# WeddingWidget.net
KiCad netlist of a schematic drawn in EAGLE
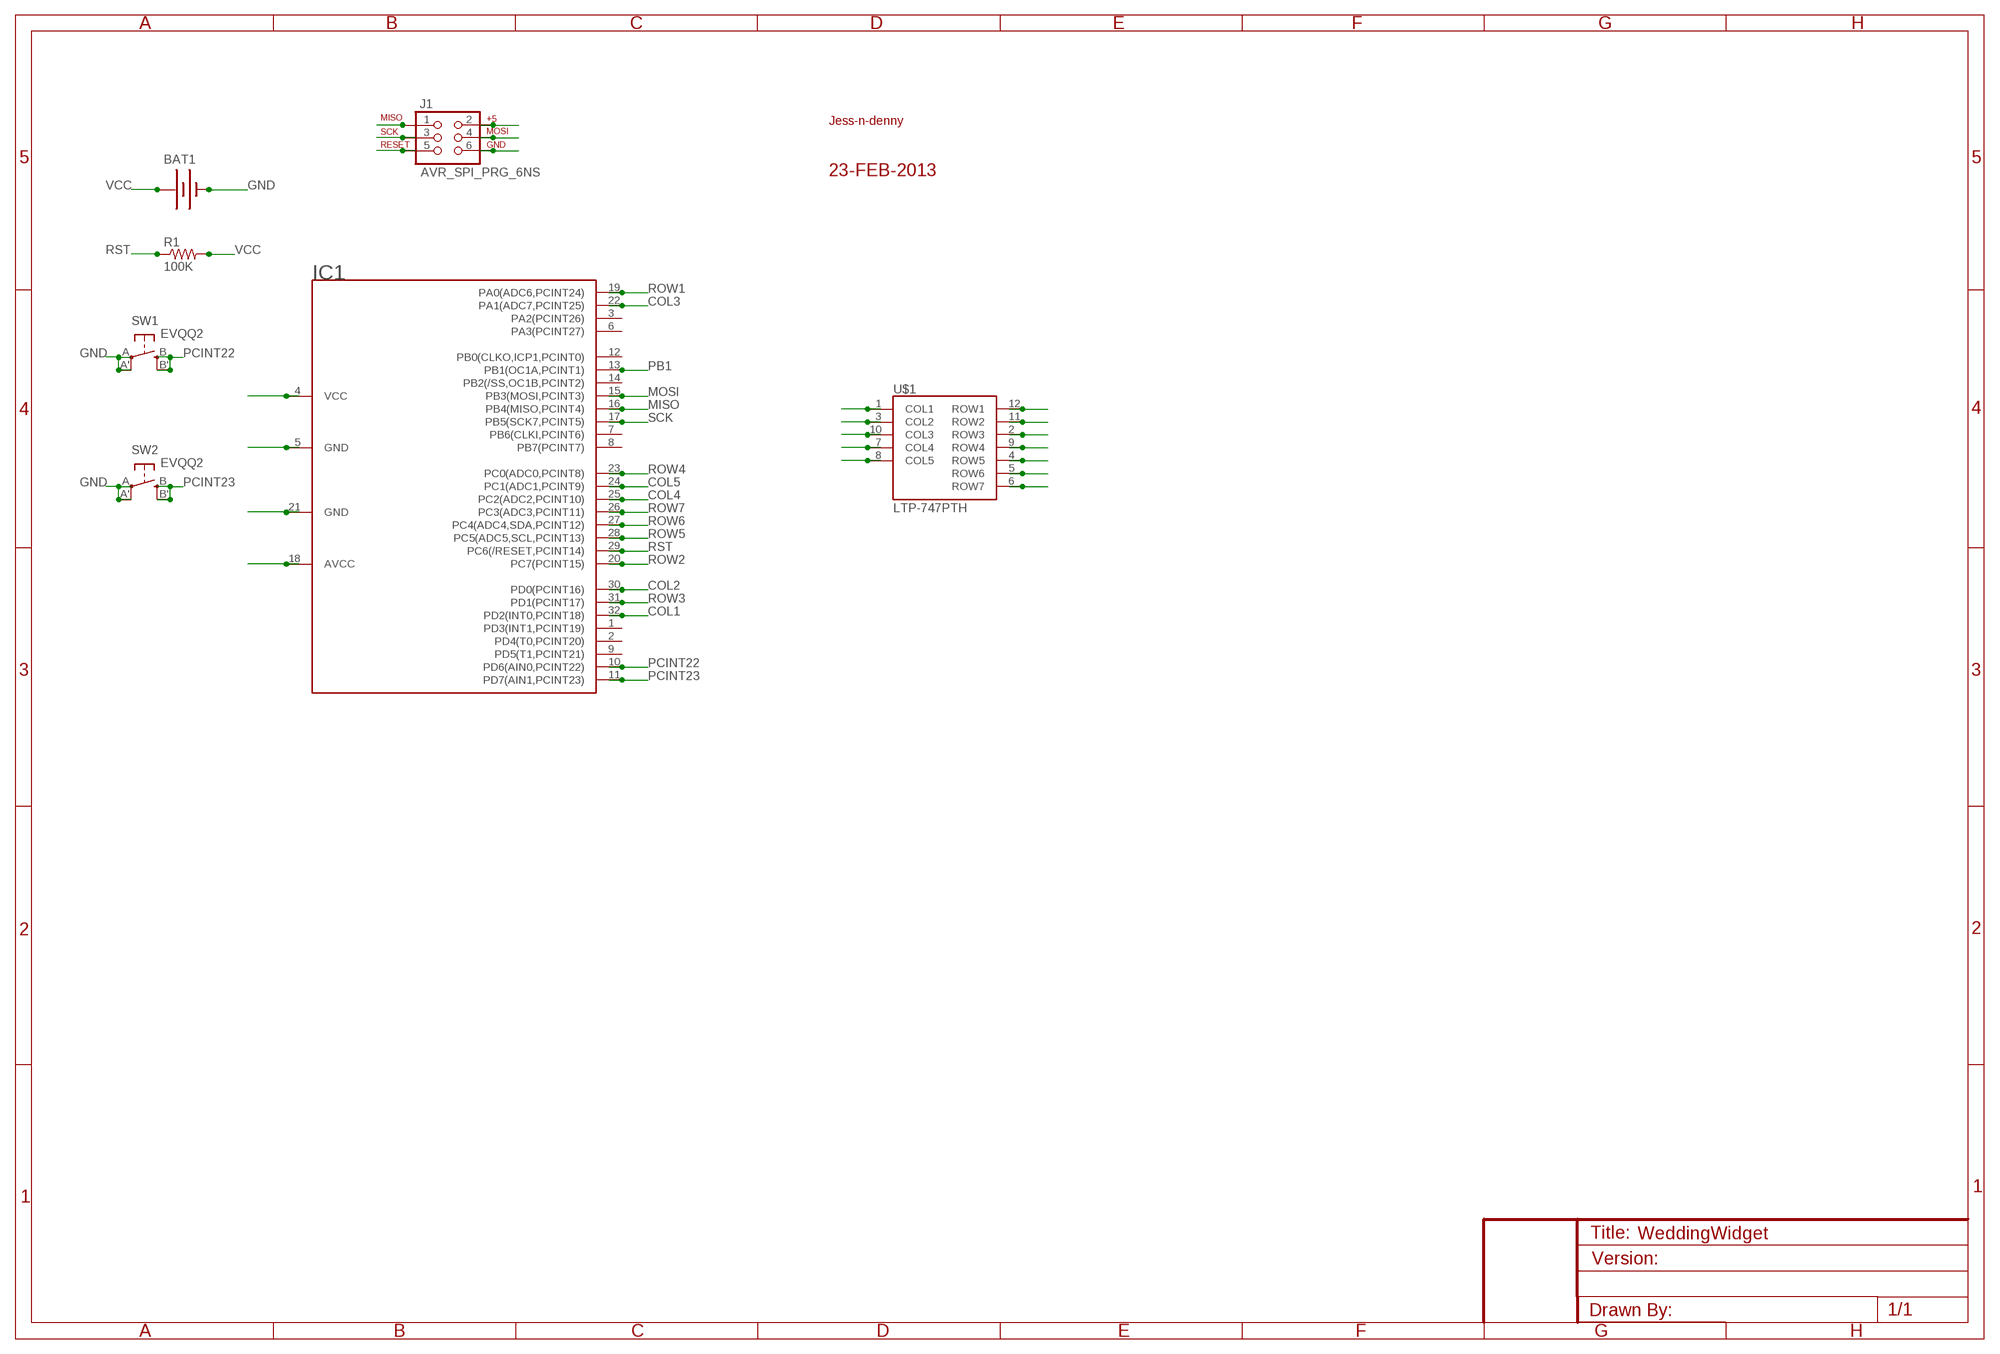
[diagram p0: schematic, sheet 1]

(export (version "E")
  (design (tool "Eeschema 10.0.6"))
  (components
    (comp (ref "BAT1")
      (value "BATTERY12MM")
      (footprint "eagle-import:BATTCON_12MM")
      (libsource (lib "eagle-import") (part "BATTERY12MM"))
    )
    (comp (ref "IC1")
      (value "ATTINY88")
      (footprint "eagle-import:TQFP32-08")
      (libsource (lib "eagle-import") (part "ATTINY88"))
    )
    (comp (ref "J1")
      (value "AVR_SPI_PRG_6NS")
      (footprint "eagle-import:2X3-NS")
      (libsource (lib "eagle-import") (part "AVR_SPI_PRG_6NS"))
    )
    (comp (ref "R1")
      (value "100K")
      (footprint "eagle-import:M0805")
      (libsource (lib "eagle-import") (part "R-US_M0805"))
    )
    (comp (ref "SW1")
      (value "EVQQ2")
      (footprint "eagle-import:EVQ-Q2")
      (libsource (lib "eagle-import") (part "EVQQ2"))
    )
    (comp (ref "SW2")
      (value "EVQQ2")
      (footprint "eagle-import:EVQ-Q2")
      (libsource (lib "eagle-import") (part "EVQQ2"))
    )
    (comp (ref "U$1")
      (value "LTP-747PTH")
      (footprint "eagle-import:LTP-747")
      (libsource (lib "eagle-import") (part "LTP-747PTH"))
    )
    (comp (ref "U$2")
      (value "JESS-N-DENNY")
      (footprint "eagle-import:JESS-N-DENNY")
      (libsource (lib "eagle-import") (part "JESS-N-DENNY"))
    )
    (comp (ref "U$3")
      (value "23FEB2013")
      (footprint "eagle-import:23FEB2013")
      (libsource (lib "eagle-import") (part "23FEB2013"))
    )
  )
  (nets
    (net (code "1") (name "/COL1") (class "Default")
      (node (ref "IC1") (pin "32") (pinfunction "PD2(INT0,PCINT18)_32") (pintype "bidirectional"))
      (node (ref "U$1") (pin "1") (pinfunction "COL1_1") (pintype "bidirectional"))
    )
    (net (code "2") (name "/COL2") (class "Default")
      (node (ref "IC1") (pin "30") (pinfunction "PD0(PCINT16)_30") (pintype "bidirectional"))
      (node (ref "U$1") (pin "3") (pinfunction "COL2_3") (pintype "bidirectional"))
    )
    (net (code "3") (name "/COL3") (class "Default")
      (node (ref "IC1") (pin "22") (pinfunction "PA1(ADC7,PCINT25)_22") (pintype "bidirectional"))
      (node (ref "U$1") (pin "10") (pinfunction "COL3_10") (pintype "bidirectional"))
    )
    (net (code "4") (name "/COL4") (class "Default")
      (node (ref "IC1") (pin "25") (pinfunction "PC2(ADC2,PCINT10)_25") (pintype "bidirectional"))
      (node (ref "U$1") (pin "7") (pinfunction "COL4_7") (pintype "bidirectional"))
    )
    (net (code "5") (name "/COL5") (class "Default")
      (node (ref "IC1") (pin "24") (pinfunction "PC1(ADC1,PCINT9)_24") (pintype "bidirectional"))
      (node (ref "U$1") (pin "8") (pinfunction "COL5_8") (pintype "bidirectional"))
    )
    (net (code "6") (name "/GND") (class "Default")
      (node (ref "BAT1") (pin "GND") (pinfunction "-_GND") (pintype "power_in"))
      (node (ref "IC1") (pin "21") (pinfunction "GND_21") (pintype "power_in"))
      (node (ref "IC1") (pin "5") (pinfunction "GND_5") (pintype "power_in"))
      (node (ref "J1") (pin "6") (pinfunction "6_6") (pintype "passive"))
      (node (ref "SW1") (pin "A") (pinfunction "P_A") (pintype "passive"))
      (node (ref "SW1") (pin "A'") (pinfunction "P1_A'") (pintype "passive"))
      (node (ref "SW2") (pin "A") (pinfunction "P_A") (pintype "passive"))
      (node (ref "SW2") (pin "A'") (pinfunction "P1_A'") (pintype "passive"))
    )
    (net (code "7") (name "/MISO") (class "Default")
      (node (ref "IC1") (pin "16") (pinfunction "PB4(MISO,PCINT4)_16") (pintype "bidirectional"))
      (node (ref "J1") (pin "1") (pinfunction "1_1") (pintype "passive"))
    )
    (net (code "8") (name "/MOSI") (class "Default")
      (node (ref "IC1") (pin "15") (pinfunction "PB3(MOSI,PCINT3)_15") (pintype "bidirectional"))
      (node (ref "J1") (pin "4") (pinfunction "4_4") (pintype "passive"))
    )
    (net (code "9") (name "/PB1") (class "Default")
      (node (ref "IC1") (pin "13") (pinfunction "PB1(OC1A,PCINT1)_13") (pintype "bidirectional"))
    )
    (net (code "10") (name "/PCINT22") (class "Default")
      (node (ref "IC1") (pin "10") (pinfunction "PD6(AIN0,PCINT22)_10") (pintype "bidirectional"))
      (node (ref "SW1") (pin "B") (pinfunction "S_B") (pintype "passive"))
      (node (ref "SW1") (pin "B'") (pinfunction "S1_B'") (pintype "passive"))
    )
    (net (code "11") (name "/PCINT23") (class "Default")
      (node (ref "IC1") (pin "11") (pinfunction "PD7(AIN1,PCINT23)_11") (pintype "bidirectional"))
      (node (ref "SW2") (pin "B") (pinfunction "S_B") (pintype "passive"))
      (node (ref "SW2") (pin "B'") (pinfunction "S1_B'") (pintype "passive"))
    )
    (net (code "12") (name "/ROW1") (class "Default")
      (node (ref "IC1") (pin "19") (pinfunction "PA0(ADC6,PCINT24)_19") (pintype "bidirectional"))
      (node (ref "U$1") (pin "12") (pinfunction "ROW1_12") (pintype "bidirectional"))
    )
    (net (code "13") (name "/ROW2") (class "Default")
      (node (ref "IC1") (pin "20") (pinfunction "PC7(PCINT15)_20") (pintype "bidirectional"))
      (node (ref "U$1") (pin "11") (pinfunction "ROW2_11") (pintype "bidirectional"))
    )
    (net (code "14") (name "/ROW3") (class "Default")
      (node (ref "IC1") (pin "31") (pinfunction "PD1(PCINT17)_31") (pintype "bidirectional"))
      (node (ref "U$1") (pin "2") (pinfunction "ROW3_2") (pintype "bidirectional"))
    )
    (net (code "15") (name "/ROW4") (class "Default")
      (node (ref "IC1") (pin "23") (pinfunction "PC0(ADC0,PCINT8)_23") (pintype "bidirectional"))
      (node (ref "U$1") (pin "9") (pinfunction "ROW4_9") (pintype "bidirectional"))
    )
    (net (code "16") (name "/ROW5") (class "Default")
      (node (ref "IC1") (pin "28") (pinfunction "PC5(ADC5,SCL,PCINT13)_28") (pintype "bidirectional"))
      (node (ref "U$1") (pin "4") (pinfunction "ROW5_4") (pintype "bidirectional"))
    )
    (net (code "17") (name "/ROW6") (class "Default")
      (node (ref "IC1") (pin "27") (pinfunction "PC4(ADC4,SDA,PCINT12)_27") (pintype "bidirectional"))
      (node (ref "U$1") (pin "5") (pinfunction "ROW6_5") (pintype "bidirectional"))
    )
    (net (code "18") (name "/ROW7") (class "Default")
      (node (ref "IC1") (pin "26") (pinfunction "PC3(ADC3,PCINT11)_26") (pintype "bidirectional"))
      (node (ref "U$1") (pin "6") (pinfunction "ROW7_6") (pintype "bidirectional"))
    )
    (net (code "19") (name "/RST") (class "Default")
      (node (ref "IC1") (pin "29") (pinfunction "PC6(/RESET,PCINT14)_29") (pintype "bidirectional"))
      (node (ref "J1") (pin "5") (pinfunction "5_5") (pintype "passive"))
      (node (ref "R1") (pin "1") (pinfunction "1_1") (pintype "passive"))
    )
    (net (code "20") (name "/SCK") (class "Default")
      (node (ref "IC1") (pin "17") (pinfunction "PB5(SCK7,PCINT5)_17") (pintype "bidirectional"))
      (node (ref "J1") (pin "3") (pinfunction "3_3") (pintype "passive"))
    )
    (net (code "21") (name "/VCC") (class "Default")
      (node (ref "BAT1") (pin "V+") (pinfunction "+_V+") (pintype "power_in"))
      (node (ref "IC1") (pin "18") (pinfunction "AVCC_18") (pintype "power_in"))
      (node (ref "IC1") (pin "4") (pinfunction "VCC_4") (pintype "power_in"))
      (node (ref "J1") (pin "2") (pinfunction "2_2") (pintype "passive"))
      (node (ref "R1") (pin "2") (pinfunction "2_2") (pintype "passive"))
    )
    (net (code "22") (name "unconnected-(IC1-PA2(PCINT26)-Pad3)") (class "Default")
      (node (ref "IC1") (pin "3") (pinfunction "PA2(PCINT26)_3") (pintype "bidirectional"))
    )
    (net (code "23") (name "unconnected-(IC1-PA3(PCINT27)-Pad6)") (class "Default")
      (node (ref "IC1") (pin "6") (pinfunction "PA3(PCINT27)_6") (pintype "bidirectional"))
    )
    (net (code "24") (name "unconnected-(IC1-PB0(CLKO,ICP1,PCINT0)-Pad12)") (class "Default")
      (node (ref "IC1") (pin "12") (pinfunction "PB0(CLKO,ICP1,PCINT0)_12") (pintype "bidirectional"))
    )
    (net (code "25") (name "unconnected-(IC1-PB2({slash}SS,OC1B,PCINT2)-Pad14)") (class "Default")
      (node (ref "IC1") (pin "14") (pinfunction "PB2(/SS,OC1B,PCINT2)_14") (pintype "bidirectional"))
    )
    (net (code "26") (name "unconnected-(IC1-PB6(CLKI,PCINT6)-Pad7)") (class "Default")
      (node (ref "IC1") (pin "7") (pinfunction "PB6(CLKI,PCINT6)_7") (pintype "bidirectional"))
    )
    (net (code "27") (name "unconnected-(IC1-PB7(PCINT7)-Pad8)") (class "Default")
      (node (ref "IC1") (pin "8") (pinfunction "PB7(PCINT7)_8") (pintype "bidirectional"))
    )
    (net (code "28") (name "unconnected-(IC1-PD3(INT1,PCINT19)-Pad1)") (class "Default")
      (node (ref "IC1") (pin "1") (pinfunction "PD3(INT1,PCINT19)_1") (pintype "bidirectional"))
    )
    (net (code "29") (name "unconnected-(IC1-PD4(T0,PCINT20)-Pad2)") (class "Default")
      (node (ref "IC1") (pin "2") (pinfunction "PD4(T0,PCINT20)_2") (pintype "bidirectional"))
    )
    (net (code "30") (name "unconnected-(IC1-PD5(T1,PCINT21)-Pad9)") (class "Default")
      (node (ref "IC1") (pin "9") (pinfunction "PD5(T1,PCINT21)_9") (pintype "bidirectional"))
    )
  )
)
